# 433TMP.net
KiCad netlist of a schematic drawn in EAGLE
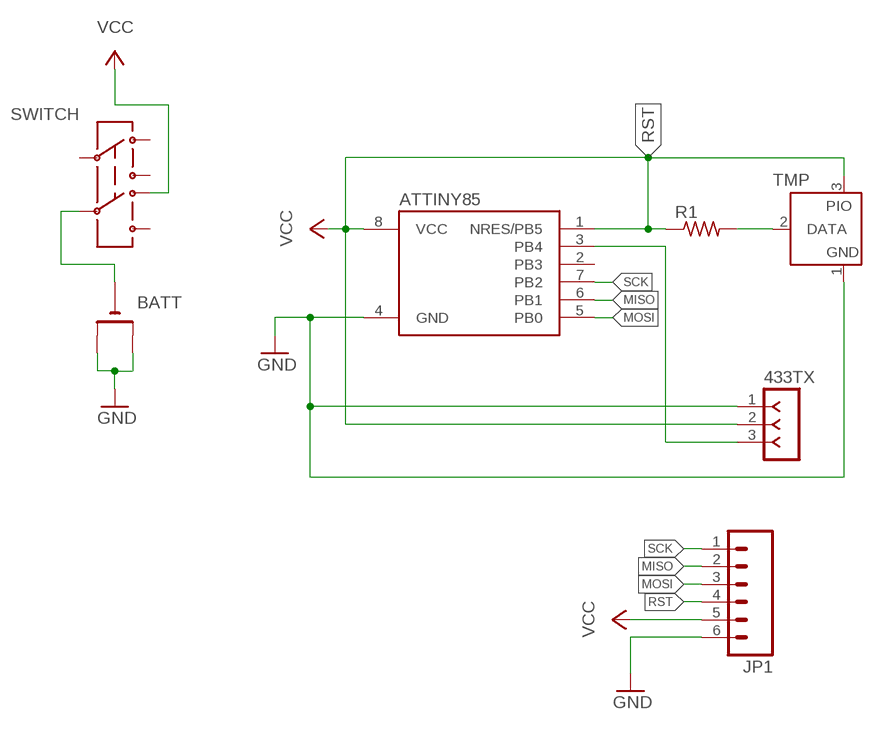
[diagram p0: schematic, sheet 1]

(export (version "E")
  (design (tool "Eeschema 10.0.6"))
  (components
    (comp (ref "433TX")
      (value "F-1X03-SIP-100-40")
      (footprint "eagle-import:SIP-100-03-40")
      (libsource (lib "eagle-import") (part "F-1X03-SIP-100-40"))
    )
    (comp (ref "ATTINY85")
      (value "ATTINY85-S")
      (footprint "eagle-import:SOIC8_EIAJ_208MIL")
      (libsource (lib "eagle-import") (part "ATTINY85S-"))
    )
    (comp (ref "BATT")
      (value "CR2032SMT")
      (footprint "eagle-import:CR2032-SMD")
      (libsource (lib "eagle-import") (part "CR2032SMT"))
    )
    (comp (ref "JP1")
      (value "M06SILK_FEMALE_PTH")
      (footprint "eagle-import:1X06")
      (libsource (lib "eagle-import") (part "M06SILK_FEMALE_PTH"))
    )
    (comp (ref "R1")
      (value "R-US_R0805")
      (footprint "eagle-import:R0805")
      (libsource (lib "eagle-import") (part "R-US_R0805"))
    )
    (comp (ref "SWITCH")
      (value "AYZ0202")
      (footprint "eagle-import:AYZ0202")
      (libsource (lib "eagle-import") (part "AYZ0202"))
    )
    (comp (ref "TMP")
      (value "DS2405")
      (footprint "eagle-import:TO92-")
      (fields (field (name "MF") "DALLAS SEMICONDUCTOR"))
      (libsource (lib "eagle-import") (part "DS2405"))
    )
  )
  (nets
    (net (code "1") (name "GND") (class "Default")
      (node (ref "433TX") (pin "1") (pinfunction "1_1") (pintype "passive"))
      (node (ref "ATTINY85") (pin "4") (pinfunction "GND_4") (pintype "power_in"))
      (node (ref "BATT") (pin "+$1") (pinfunction "+_+$1") (pintype "passive"))
      (node (ref "BATT") (pin "+$2") (pinfunction "+1_+$2") (pintype "passive"))
      (node (ref "JP1") (pin "6") (pinfunction "6_6") (pintype "passive"))
      (node (ref "TMP") (pin "1") (pinfunction "GND_1") (pintype "passive"))
    )
    (net (code "2") (name "MISO") (class "Default")
      (node (ref "ATTINY85") (pin "6") (pinfunction "PB1_6") (pintype "bidirectional"))
      (node (ref "JP1") (pin "2") (pinfunction "2_2") (pintype "passive"))
    )
    (net (code "3") (name "MOSI") (class "Default")
      (node (ref "ATTINY85") (pin "5") (pinfunction "PB0_5") (pintype "bidirectional"))
      (node (ref "JP1") (pin "3") (pinfunction "3_3") (pintype "passive"))
    )
    (net (code "4") (name "Net-(ATTINY85-PB4)") (class "Default")
      (node (ref "433TX") (pin "3") (pinfunction "3_3") (pintype "passive"))
      (node (ref "ATTINY85") (pin "3") (pinfunction "PB4_3") (pintype "bidirectional"))
    )
    (net (code "5") (name "Net-(BATT-Pad-)") (class "Default")
      (node (ref "BATT") (pin "-") (pinfunction "-_-") (pintype "passive"))
      (node (ref "SWITCH") (pin "5") (pinfunction "5_5") (pintype "bidirectional"))
    )
    (net (code "6") (name "Net-(TMP-DATA)") (class "Default")
      (node (ref "R1") (pin "2") (pinfunction "2_2") (pintype "passive"))
      (node (ref "TMP") (pin "2") (pinfunction "DATA_2") (pintype "input"))
    )
    (net (code "7") (name "RST") (class "Default")
      (node (ref "433TX") (pin "2") (pinfunction "2_2") (pintype "passive"))
      (node (ref "ATTINY85") (pin "1") (pinfunction "NRES/PB5_1") (pintype "bidirectional"))
      (node (ref "ATTINY85") (pin "8") (pinfunction "VCC_8") (pintype "power_in"))
      (node (ref "JP1") (pin "4") (pinfunction "4_4") (pintype "passive"))
      (node (ref "JP1") (pin "5") (pinfunction "5_5") (pintype "passive"))
      (node (ref "R1") (pin "1") (pinfunction "1_1") (pintype "passive"))
      (node (ref "SWITCH") (pin "6") (pinfunction "4_6") (pintype "bidirectional"))
      (node (ref "TMP") (pin "3") (pinfunction "PIO_3") (pintype "passive"))
    )
    (net (code "8") (name "SCK") (class "Default")
      (node (ref "ATTINY85") (pin "7") (pinfunction "PB2_7") (pintype "bidirectional"))
      (node (ref "JP1") (pin "1") (pinfunction "1_1") (pintype "passive"))
    )
    (net (code "9") (name "unconnected-(ATTINY85-PB3-Pad2)") (class "Default")
      (node (ref "ATTINY85") (pin "2") (pinfunction "PB3_2") (pintype "bidirectional"))
    )
    (net (code "10") (name "unconnected-(SWITCH-1-Pad3)") (class "Default")
      (node (ref "SWITCH") (pin "3") (pinfunction "1_3") (pintype "bidirectional"))
    )
    (net (code "11") (name "unconnected-(SWITCH-3-Pad1)") (class "Default")
      (node (ref "SWITCH") (pin "1") (pinfunction "3_1") (pintype "bidirectional"))
    )
    (net (code "12") (name "unconnected-(SWITCH-6-Pad4)") (class "Default")
      (node (ref "SWITCH") (pin "4") (pinfunction "6_4") (pintype "bidirectional"))
    )
    (net (code "13") (name "unconnected-(SWITCH-Pad2)") (class "Default")
      (node (ref "SWITCH") (pin "2") (pinfunction "2_2") (pintype "bidirectional"))
    )
  )
)
